# rf.net
KiCad netlist of a schematic drawn in Altium Designer
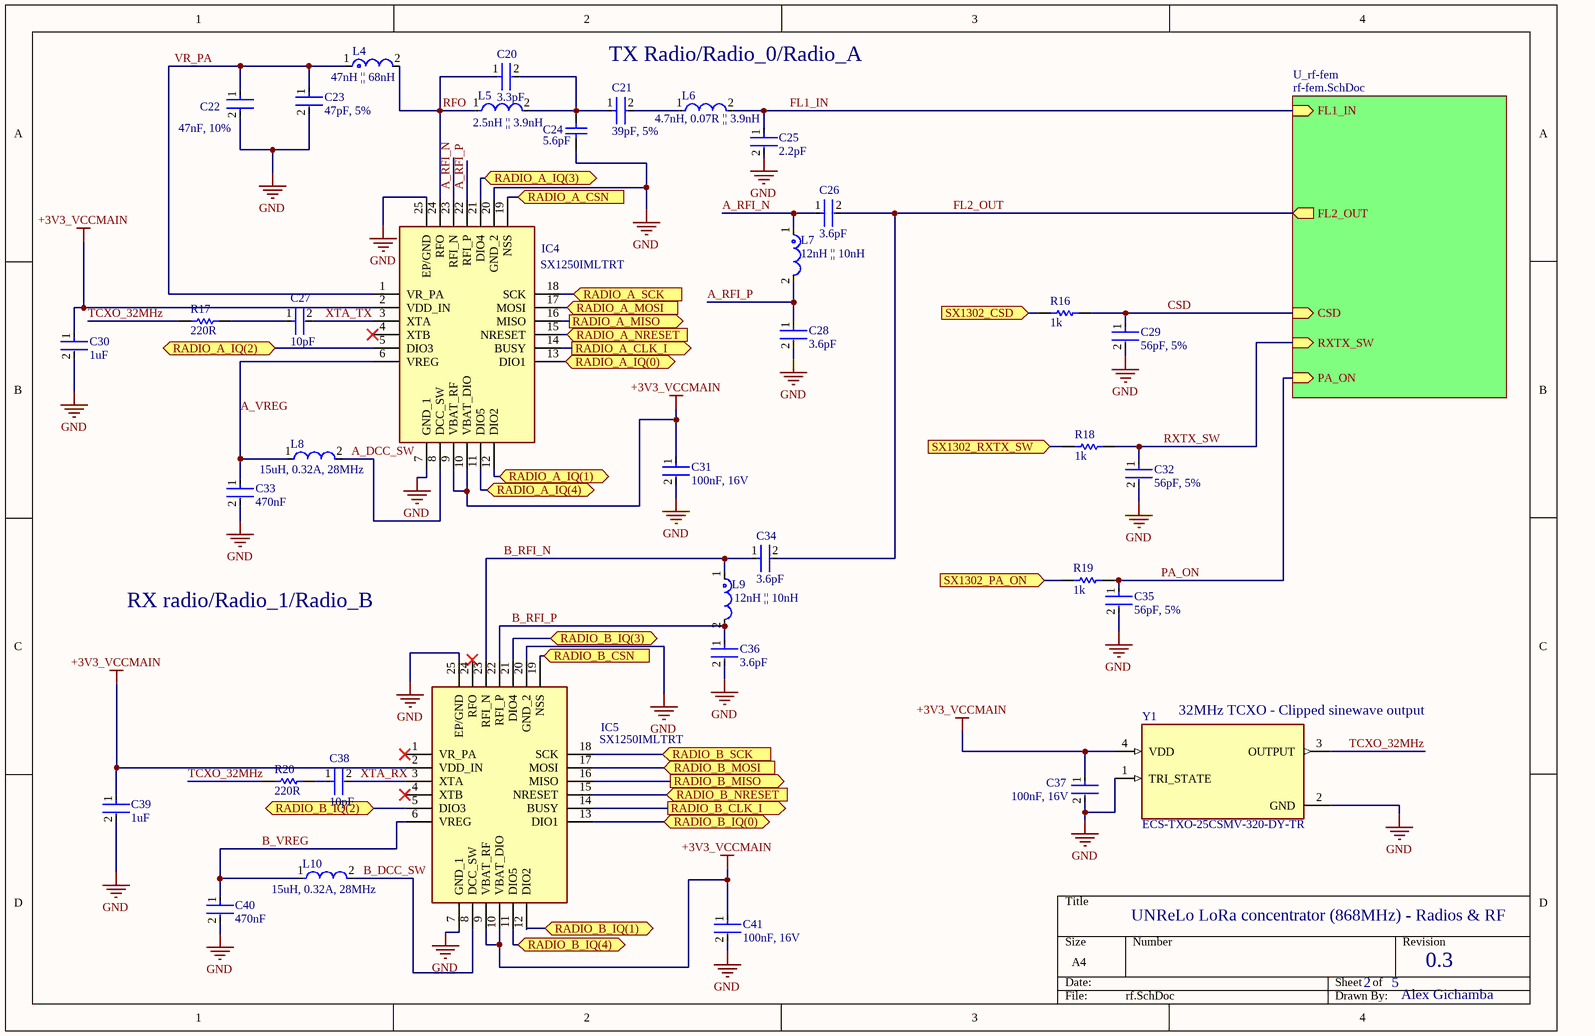
[diagram p0: rf.SchDoc]

(export (version "E")
  (design (tool "Eeschema 10.0.6"))
  (components
    (comp (ref "C20")
      (value "3.3pF")
      (footprint "FP-GQM187-0_15-MFG")
      (description "Ceramic Capacitor 3.3pF ±0.1pF 250VDC C0G 0603 Paper T/R")
      (libsource (lib "Altium Content Vault") (part "02cd4be3c70576c341d710602a673aa"))
    )
    (comp (ref "C21")
      (value "39pF, 5%")
      (footprint "FP-CL10-IPC_B")
      (description "Cap Ceramic 39pF 50V C0G ±5% Pad SMD 0603 +125°C T/R")
      (fields (field (name "TOLERANCE") "5%") (field (name "VOLTAGE") "50V"))
      (libsource (lib "Altium Content Vault") (part "b4654b650e69147ec39a6b967a45e02"))
    )
    (comp (ref "C22")
      (value "47nF, 10%")
      (footprint "FP-CL10-IPC_A")
      (description "Cap Ceramic 47nF 50V X7R ±10% Pad SMD 0603 +125°C T/R")
      (fields (field (name "TOLERANCE") "10%") (field (name "VOLTAGE") "50V"))
      (libsource (lib "Altium Content Vault") (part "b4654b650e69147ec39a6b967a45e02"))
    )
    (comp (ref "C23")
      (value "47pF, 5%")
      (footprint "FP-0603-L_1_6_0_15-W_0_81-MFG")
      (description "General Purpose Ceramic Capacitor, 0603, 47pF, 5%, NP0, 30ppm/°C, 50V")
      (fields (field (name "TOLERANCE") "5%") (field (name "VOLTAGE") "50V"))
      (libsource (lib "Altium Content Vault") (part "02cd4be3c70576c341d710602a673aa"))
    )
    (comp (ref "C24")
      (value "5.6pF")
      (footprint "CAPC1608X90X35ML10T15")
      (fields (field (name "MANUFACTURER") "Murata") (field (name "PART NUMBER") "GRM1885C1H5R6BA01D"))
      (libsource (lib "Altium Content Vault") (part "CAP"))
    )
    (comp (ref "C25")
      (value "2.2pF")
      (footprint "FP-CL764-IPC_C")
      (description "Cap Ceramic 2.2pF 50V C0G ±0.1pF SMD 0402 +125°C Paper T/R")
      (fields (field (name "VOLTAGE") "50V"))
      (libsource (lib "Altium Content Vault") (part "b4654b650e69147ec39a6b967a45e02"))
    )
    (comp (ref "C26")
      (value "3.6pF")
      (footprint "FP-GJM155-0_05-IPC_C")
      (description "Multi-Layer Ceramic Capacitor 3.6pF C0G  ±0.1pF 0402 Paper T/R")
      (libsource (lib "Altium Content Vault") (part "02cd4be3c70576c341d710602a673aa"))
    )
    (comp (ref "C27")
      (value "10pF")
      (footprint "FP-CL10-IPC_A")
      (description "Cap Ceramic 10pF 50V C0G ±5% Pad SMD 0603 +125°C T/R")
      (fields (field (name "VOLTAGE") "50V") (field (name "TOLERANCE") "5%"))
      (libsource (lib "Altium Content Vault") (part "b4654b650e69147ec39a6b967a45e02"))
    )
    (comp (ref "C28")
      (value "3.6pF")
      (footprint "FP-GJM155-0_05-IPC_C")
      (description "Multi-Layer Ceramic Capacitor 3.6pF C0G  ±0.1pF 0402 Paper T/R")
      (libsource (lib "Altium Content Vault") (part "02cd4be3c70576c341d710602a673aa"))
    )
    (comp (ref "C29")
      (value "56pF, 5%")
      (footprint "FP-GCM188-0_1-IPC_A")
      (description "Ceramic Capacitor for Automotive 56pF  ±5% 100VDC C0G 0603 Paper T/R")
      (fields (field (name "TOLERANCE") "5%"))
      (libsource (lib "Altium Content Vault") (part "02cd4be3c70576c341d710602a673aa"))
    )
    (comp (ref "C30")
      (value "1uF")
      (footprint "FP-CL21-IPC_A")
      (description "CL21 Series 0805 1uF 16V ±10% Tolerance X7R Multilayer Ceramic Chip Capacitor")
      (fields (field (name "TOLERANCE") "10%") (field (name "VOLTAGE") "16V"))
      (libsource (lib "Altium Content Vault") (part "b4654b650e69147ec39a6b967a45e02"))
    )
    (comp (ref "C31")
      (value "100nF, 16V")
      (footprint "FP-CC0603-DA-MFG")
      (description "CAP CER 0.1UF 50V X7R 0603")
      (fields (field (name "MANUFACTURER") "YAGEO") (field (name "VOLTAGE") "50 V"))
      (libsource (lib "Altium Content Vault") (part "11868f565c42a9108669ba33697ecf6"))
    )
    (comp (ref "C32")
      (value "56pF, 5%")
      (footprint "FP-GCM188-0_1-IPC_A")
      (description "Ceramic Capacitor for Automotive 56pF  ±5% 100VDC C0G 0603 Paper T/R")
      (fields (field (name "TOLERANCE") "5%"))
      (libsource (lib "Altium Content Vault") (part "02cd4be3c70576c341d710602a673aa"))
    )
    (comp (ref "C33")
      (value "470nF")
      (footprint "FP-0603-L_1_6_0_1-W_0_8_0-IPC_A")
      (description "None")
      (fields (field (name "TOLERANCE") "10%"))
      (libsource (lib "Altium Content Vault") (part "02cd4be3c70576c341d710602a673aa"))
    )
    (comp (ref "C34")
      (value "3.6pF")
      (footprint "FP-GJM155-0_05-IPC_C")
      (description "Multi-Layer Ceramic Capacitor 3.6pF C0G  ±0.1pF 0402 Paper T/R")
      (libsource (lib "Altium Content Vault") (part "02cd4be3c70576c341d710602a673aa"))
    )
    (comp (ref "C35")
      (value "56pF, 5%")
      (footprint "FP-GCM188-0_1-IPC_A")
      (description "Ceramic Capacitor for Automotive 56pF  ±5% 100VDC C0G 0603 Paper T/R")
      (fields (field (name "TOLERANCE") "5%"))
      (libsource (lib "Altium Content Vault") (part "02cd4be3c70576c341d710602a673aa"))
    )
    (comp (ref "C36")
      (value "3.6pF")
      (footprint "FP-GJM155-0_05-IPC_C")
      (description "Multi-Layer Ceramic Capacitor 3.6pF C0G  ±0.1pF 0402 Paper T/R")
      (libsource (lib "Altium Content Vault") (part "02cd4be3c70576c341d710602a673aa"))
    )
    (comp (ref "C37")
      (value "100nF, 16V")
      (footprint "FP-CC0603-DA-MFG")
      (description "CAP CER 0.1UF 50V X7R 0603")
      (fields (field (name "MANUFACTURER") "YAGEO") (field (name "VOLTAGE") "50 V"))
      (libsource (lib "Altium Content Vault") (part "11868f565c42a9108669ba33697ecf6"))
    )
    (comp (ref "C38")
      (value "10pF")
      (footprint "FP-CL10-IPC_A")
      (description "Cap Ceramic 10pF 50V C0G ±5% Pad SMD 0603 +125°C T/R")
      (fields (field (name "VOLTAGE") "50V") (field (name "TOLERANCE") "5%"))
      (libsource (lib "Altium Content Vault") (part "b4654b650e69147ec39a6b967a45e02"))
    )
    (comp (ref "C39")
      (value "1uF")
      (footprint "FP-CL21-IPC_A")
      (description "CL21 Series 0805 1uF 16V ±10% Tolerance X7R Multilayer Ceramic Chip Capacitor")
      (fields (field (name "TOLERANCE") "10%") (field (name "VOLTAGE") "16V"))
      (libsource (lib "Altium Content Vault") (part "b4654b650e69147ec39a6b967a45e02"))
    )
    (comp (ref "C40")
      (value "470nF")
      (footprint "FP-0603-L_1_6_0_1-W_0_8_0-IPC_A")
      (description "None")
      (fields (field (name "TOLERANCE") "10%"))
      (libsource (lib "Altium Content Vault") (part "02cd4be3c70576c341d710602a673aa"))
    )
    (comp (ref "C41")
      (value "100nF, 16V")
      (footprint "FP-CC0603-DA-MFG")
      (description "CAP CER 0.1UF 50V X7R 0603")
      (fields (field (name "MANUFACTURER") "YAGEO") (field (name "VOLTAGE") "50 V"))
      (libsource (lib "Altium Content Vault") (part "11868f565c42a9108669ba33697ecf6"))
    )
    (comp (ref "IC4")
      (value "SX1250IMLTRT")
      (footprint "QFN50P400X400X100-25N-D")
      (description "Integrated Circuit")
      (fields (field (name "MOUSER PART NUMBER") "947-SX1250IMLTRT"))
      (libsource (lib "SamacSys") (part "SX1250IMLTRT"))
    )
    (comp (ref "IC5")
      (value "SX1250IMLTRT")
      (footprint "QFN50P400X400X100-25N-D")
      (description "Integrated Circuit")
      (fields (field (name "MOUSER PART NUMBER") "947-SX1250IMLTRT"))
      (libsource (lib "SamacSys") (part "SX1250IMLTRT"))
    )
    (comp (ref "L4")
      (value "47nH Ζ 68nH")
      (footprint "FP-LQG18HH_00-MFG")
      (description "Multilayer type RF Inductor 68nH ±5% 0.8Ω 400mA 0603")
      (fields (field (name "TOLERANCE") "5%"))
      (libsource (lib "Altium Content Vault") (part "4cc4b267dca4c8e51f7102f422741d8"))
    )
    (comp (ref "L5")
      (value "2.5nH Ζ 3.9nH")
      (footprint "FP-LQW15AN_00-W0_6-0_1-MFG")
      (description "Wire Wound RF Inductor 4.7nH ±0.1nH 750mA 0.07Ω 0402 (1005)")
      (fields (field (name "TOLERANCE") "2%"))
      (libsource (lib "Altium Content Vault") (part "725321dda6339637d4d059423bc1c3c"))
    )
    (comp (ref "L6")
      (value "4.7nH, 0.07R Ζ 3.9nH")
      (footprint "FP-LQW15AN_00-W0_6-0_1-MFG")
      (description "Wire Wound RF Inductor 4.7nH ±0.1nH 750mA 0.07Ω 0402 (1005)")
      (fields (field (name "TOLERANCE") "2%"))
      (libsource (lib "Altium Content Vault") (part "725321dda6339637d4d059423bc1c3c"))
    )
    (comp (ref "L7")
      (value "12nH Ζ 10nH")
      (footprint "FP-LQG15HH_02-IPC_A")
      (description "Multilayer type RF Inductor 10nH ±5% 0.26Ω 500mA 0402")
      (fields (field (name "TOLERANCE") "5%"))
      (libsource (lib "Altium Content Vault") (part "4cc4b267dca4c8e51f7102f422741d8"))
    )
    (comp (ref "L8")
      (value "15uH, 0.32A, 28MHz")
      (footprint "FP-CB2012-MFG")
      (description "SMD Inductors 15uH ±10% 0.32A 1.69Ω 0805")
      (fields (field (name "TOLERANCE") "10%"))
      (libsource (lib "Altium Content Vault") (part "725321dda6339637d4d059423bc1c3c"))
    )
    (comp (ref "L9")
      (value "12nH Ζ 10nH")
      (footprint "FP-LQG15HH_02-IPC_A")
      (description "Multilayer type RF Inductor 10nH ±5% 0.26Ω 500mA 0402")
      (fields (field (name "TOLERANCE") "5%"))
      (libsource (lib "Altium Content Vault") (part "4cc4b267dca4c8e51f7102f422741d8"))
    )
    (comp (ref "L10")
      (value "15uH, 0.32A, 28MHz")
      (footprint "FP-CB2012-MFG")
      (description "SMD Inductors 15uH ±10% 0.32A 1.69Ω 0805")
      (fields (field (name "TOLERANCE") "10%"))
      (libsource (lib "Altium Content Vault") (part "725321dda6339637d4d059423bc1c3c"))
    )
    (comp (ref "R16")
      (value "1k")
      (footprint "RESC2013X70X40ML20T20")
      (description "Chip Resistor, 1 KOhm, +/- 1%, 0.125 W, -55 to 155 degC, 0805 (2012 Metric), RoHS, Tape and Reel")
      (fields (field (name "MANUFACTURER") "Panasonic"))
      (libsource (lib "Altium Content Vault") (part "RES-2"))
    )
    (comp (ref "R17")
      (value "220R")
      (footprint "RESC1608X55X30LL15T15")
      (description "Chip Resistor, 220 Ohm, +/- 1%, 0.1 W, -55 to 155 degC, 0603 (1608 Metric), RoHS, Tape and Reel")
      (fields (field (name "TOLERANCE") "1%"))
      (libsource (lib "Altium Content Vault") (part "RES-2"))
    )
    (comp (ref "R18")
      (value "1k")
      (footprint "RESC2013X70X40ML20T20")
      (description "Chip Resistor, 1 KOhm, +/- 1%, 0.125 W, -55 to 155 degC, 0805 (2012 Metric), RoHS, Tape and Reel")
      (fields (field (name "MANUFACTURER") "Panasonic"))
      (libsource (lib "Altium Content Vault") (part "RES-2"))
    )
    (comp (ref "R19")
      (value "1k")
      (footprint "RESC2013X70X40ML20T20")
      (description "Chip Resistor, 1 KOhm, +/- 1%, 0.125 W, -55 to 155 degC, 0805 (2012 Metric), RoHS, Tape and Reel")
      (fields (field (name "MANUFACTURER") "Panasonic"))
      (libsource (lib "Altium Content Vault") (part "RES-2"))
    )
    (comp (ref "R20")
      (value "220R")
      (footprint "RESC1608X55X30LL15T15")
      (description "Chip Resistor, 220 Ohm, +/- 1%, 0.1 W, -55 to 155 degC, 0603 (1608 Metric), RoHS, Tape and Reel")
      (fields (field (name "TOLERANCE") "1%"))
      (libsource (lib "Altium Content Vault") (part "RES-2"))
    )
    (comp (ref "Y1")
      (value "ECS-TXO-25CSMV-320-DY-TR")
      (footprint "OSC_ECS-TXO-25CSMV-320-DY-TR")
      (libsource (lib "ECS-TXO-25CSMV-320-DY-TR") (part "ECS-TXO-25CSMV-320-DY-TR"))
    )
  )
  (nets
    (net (code "1") (name "+3V3_VCCMAIN") (class "Default")
      (node (ref "C30") (pin "1") (pinfunction "1_1") (pintype "passive"))
      (node (ref "C31") (pin "1") (pinfunction "1_1") (pintype "passive"))
      (node (ref "C37") (pin "1") (pinfunction "1_1") (pintype "passive"))
      (node (ref "C39") (pin "1") (pinfunction "1_1") (pintype "passive"))
      (node (ref "C41") (pin "1") (pinfunction "1_1") (pintype "passive"))
      (node (ref "IC4") (pin "10") (pinfunction "VBAT_DIO_10") (pintype "passive"))
      (node (ref "IC4") (pin "2") (pinfunction "VDD_IN_2") (pintype "passive"))
      (node (ref "IC4") (pin "9") (pinfunction "VBAT_RF_9") (pintype "passive"))
      (node (ref "IC5") (pin "10") (pinfunction "VBAT_DIO_10") (pintype "passive"))
      (node (ref "IC5") (pin "2") (pinfunction "VDD_IN_2") (pintype "passive"))
      (node (ref "IC5") (pin "9") (pinfunction "VBAT_RF_9") (pintype "passive"))
      (node (ref "Y1") (pin "4") (pinfunction "VDD_4") (pintype "input"))
    )
    (net (code "2") (name "/A_DCC_SW") (class "Default")
      (node (ref "IC4") (pin "8") (pinfunction "DCC_SW_8") (pintype "passive"))
      (node (ref "L8") (pin "2") (pinfunction "2_2") (pintype "passive"))
    )
    (net (code "3") (name "/A_RFI_N") (class "Default")
      (node (ref "C26") (pin "1") (pinfunction "1_1") (pintype "passive"))
      (node (ref "IC4") (pin "23") (pinfunction "RFI_N_23") (pintype "passive"))
      (node (ref "L7") (pin "1") (pinfunction "1_1") (pintype "passive"))
    )
    (net (code "4") (name "/A_RFI_P") (class "Default")
      (node (ref "C28") (pin "1") (pinfunction "1_1") (pintype "passive"))
      (node (ref "IC4") (pin "22") (pinfunction "RFI_P_22") (pintype "passive"))
      (node (ref "L7") (pin "2") (pinfunction "2_2") (pintype "passive"))
    )
    (net (code "5") (name "/A_VREG") (class "Default")
      (node (ref "C33") (pin "1") (pinfunction "1_1") (pintype "passive"))
      (node (ref "IC4") (pin "6") (pinfunction "VREG_6") (pintype "passive"))
      (node (ref "L8") (pin "1") (pinfunction "1_1") (pintype "passive"))
    )
    (net (code "6") (name "/B_DCC_SW") (class "Default")
      (node (ref "IC5") (pin "8") (pinfunction "DCC_SW_8") (pintype "passive"))
      (node (ref "L10") (pin "2") (pinfunction "2_2") (pintype "passive"))
    )
    (net (code "7") (name "/B_RFI_N") (class "Default")
      (node (ref "C34") (pin "1") (pinfunction "1_1") (pintype "passive"))
      (node (ref "IC5") (pin "23") (pinfunction "RFI_N_23") (pintype "passive"))
      (node (ref "L9") (pin "1") (pinfunction "1_1") (pintype "passive"))
    )
    (net (code "8") (name "/B_RFI_P") (class "Default")
      (node (ref "C36") (pin "1") (pinfunction "1_1") (pintype "passive"))
      (node (ref "IC5") (pin "22") (pinfunction "RFI_P_22") (pintype "passive"))
      (node (ref "L9") (pin "2") (pinfunction "2_2") (pintype "passive"))
    )
    (net (code "9") (name "/B_VREG") (class "Default")
      (node (ref "C40") (pin "1") (pinfunction "1_1") (pintype "passive"))
      (node (ref "IC5") (pin "6") (pinfunction "VREG_6") (pintype "passive"))
      (node (ref "L10") (pin "1") (pinfunction "1_1") (pintype "passive"))
    )
    (net (code "10") (name "/CSD") (class "Default")
      (node (ref "C29") (pin "1") (pinfunction "1_1") (pintype "passive"))
      (node (ref "R16") (pin "2") (pinfunction "2_2") (pintype "passive"))
    )
    (net (code "11") (name "/FL1_IN") (class "Default")
      (node (ref "C25") (pin "1") (pinfunction "1_1") (pintype "passive"))
      (node (ref "L6") (pin "2") (pinfunction "2_2") (pintype "passive"))
    )
    (net (code "12") (name "/FL2_OUT") (class "Default")
      (node (ref "C26") (pin "2") (pinfunction "2_2") (pintype "passive"))
      (node (ref "C34") (pin "2") (pinfunction "2_2") (pintype "passive"))
    )
    (net (code "13") (name "/PA_ON") (class "Default")
      (node (ref "C35") (pin "1") (pinfunction "1_1") (pintype "passive"))
      (node (ref "R19") (pin "2") (pinfunction "2_2") (pintype "passive"))
    )
    (net (code "14") (name "/RADIO_A_CLK_I") (class "Default")
      (node (ref "IC4") (pin "14") (pinfunction "BUSY_14") (pintype "passive"))
    )
    (net (code "15") (name "/RADIO_A_CSN") (class "Default")
      (node (ref "IC4") (pin "19") (pinfunction "NSS_19") (pintype "passive"))
    )
    (net (code "16") (name "/RADIO_A_IQ(0)") (class "Default")
      (node (ref "IC4") (pin "13") (pinfunction "DIO1_13") (pintype "passive"))
    )
    (net (code "17") (name "/RADIO_A_IQ(1)") (class "Default")
      (node (ref "IC4") (pin "12") (pinfunction "DIO2_12") (pintype "passive"))
    )
    (net (code "18") (name "/RADIO_A_IQ(2)") (class "Default")
      (node (ref "IC4") (pin "5") (pinfunction "DIO3_5") (pintype "passive"))
    )
    (net (code "19") (name "/RADIO_A_IQ(3)") (class "Default")
      (node (ref "IC4") (pin "21") (pinfunction "DIO4_21") (pintype "passive"))
    )
    (net (code "20") (name "/RADIO_A_IQ(4)") (class "Default")
      (node (ref "IC4") (pin "11") (pinfunction "DIO5_11") (pintype "passive"))
    )
    (net (code "21") (name "/RADIO_A_MISO") (class "Default")
      (node (ref "IC4") (pin "16") (pinfunction "MISO_16") (pintype "passive"))
    )
    (net (code "22") (name "/RADIO_A_MOSI") (class "Default")
      (node (ref "IC4") (pin "17") (pinfunction "MOSI_17") (pintype "passive"))
    )
    (net (code "23") (name "/RADIO_A_NRESET") (class "Default")
      (node (ref "IC4") (pin "15") (pinfunction "NRESET_15") (pintype "passive"))
    )
    (net (code "24") (name "/RADIO_A_SCK") (class "Default")
      (node (ref "IC4") (pin "18") (pinfunction "SCK_18") (pintype "passive"))
    )
    (net (code "25") (name "/RADIO_B_CLK_I") (class "Default")
      (node (ref "IC5") (pin "14") (pinfunction "BUSY_14") (pintype "passive"))
    )
    (net (code "26") (name "/RADIO_B_CSN") (class "Default")
      (node (ref "IC5") (pin "19") (pinfunction "NSS_19") (pintype "passive"))
    )
    (net (code "27") (name "/RADIO_B_IQ(0)") (class "Default")
      (node (ref "IC5") (pin "13") (pinfunction "DIO1_13") (pintype "passive"))
    )
    (net (code "28") (name "/RADIO_B_IQ(1)") (class "Default")
      (node (ref "IC5") (pin "12") (pinfunction "DIO2_12") (pintype "passive"))
    )
    (net (code "29") (name "/RADIO_B_IQ(2)") (class "Default")
      (node (ref "IC5") (pin "5") (pinfunction "DIO3_5") (pintype "passive"))
    )
    (net (code "30") (name "/RADIO_B_IQ(3)") (class "Default")
      (node (ref "IC5") (pin "21") (pinfunction "DIO4_21") (pintype "passive"))
    )
    (net (code "31") (name "/RADIO_B_IQ(4)") (class "Default")
      (node (ref "IC5") (pin "11") (pinfunction "DIO5_11") (pintype "passive"))
    )
    (net (code "32") (name "/RADIO_B_MISO") (class "Default")
      (node (ref "IC5") (pin "16") (pinfunction "MISO_16") (pintype "passive"))
    )
    (net (code "33") (name "/RADIO_B_MOSI") (class "Default")
      (node (ref "IC5") (pin "17") (pinfunction "MOSI_17") (pintype "passive"))
    )
    (net (code "34") (name "/RADIO_B_NRESET") (class "Default")
      (node (ref "IC5") (pin "15") (pinfunction "NRESET_15") (pintype "passive"))
    )
    (net (code "35") (name "/RADIO_B_SCK") (class "Default")
      (node (ref "IC5") (pin "18") (pinfunction "SCK_18") (pintype "passive"))
    )
    (net (code "36") (name "/RFO") (class "Default")
      (node (ref "C20") (pin "1") (pinfunction "1_1") (pintype "passive"))
      (node (ref "IC4") (pin "24") (pinfunction "RFO_24") (pintype "passive"))
      (node (ref "L4") (pin "2") (pinfunction "2_2") (pintype "passive"))
      (node (ref "L5") (pin "1") (pinfunction "1_1") (pintype "passive"))
    )
    (net (code "37") (name "/RXTX_SW") (class "Default")
      (node (ref "C32") (pin "1") (pinfunction "1_1") (pintype "passive"))
      (node (ref "R18") (pin "2") (pinfunction "2_2") (pintype "passive"))
    )
    (net (code "38") (name "/SX1302_CSD") (class "Default")
      (node (ref "R16") (pin "1") (pinfunction "1_1") (pintype "passive"))
    )
    (net (code "39") (name "/SX1302_PA_ON") (class "Default")
      (node (ref "R19") (pin "1") (pinfunction "1_1") (pintype "passive"))
    )
    (net (code "40") (name "/SX1302_RXTX_SW") (class "Default")
      (node (ref "R18") (pin "1") (pinfunction "1_1") (pintype "passive"))
    )
    (net (code "41") (name "/TCXO_32MHz") (class "Default")
      (node (ref "R17") (pin "1") (pinfunction "1_1") (pintype "passive"))
      (node (ref "R20") (pin "1") (pinfunction "1_1") (pintype "passive"))
      (node (ref "Y1") (pin "3") (pinfunction "OUTPUT_3") (pintype "output"))
    )
    (net (code "42") (name "/VR_PA") (class "Default")
      (node (ref "C22") (pin "1") (pinfunction "1_1") (pintype "passive"))
      (node (ref "C23") (pin "1") (pinfunction "1_1") (pintype "passive"))
      (node (ref "IC4") (pin "1") (pinfunction "VR_PA_1") (pintype "passive"))
      (node (ref "L4") (pin "1") (pinfunction "1_1") (pintype "passive"))
    )
    (net (code "43") (name "/XTA_RX") (class "Default")
      (node (ref "C38") (pin "2") (pinfunction "2_2") (pintype "passive"))
      (node (ref "IC5") (pin "3") (pinfunction "XTA_3") (pintype "passive"))
    )
    (net (code "44") (name "/XTA_TX") (class "Default")
      (node (ref "C27") (pin "2") (pinfunction "2_2") (pintype "passive"))
      (node (ref "IC4") (pin "3") (pinfunction "XTA_3") (pintype "passive"))
    )
    (net (code "45") (name "GND") (class "Default")
      (node (ref "C22") (pin "2") (pinfunction "2_2") (pintype "passive"))
      (node (ref "C23") (pin "2") (pinfunction "2_2") (pintype "passive"))
      (node (ref "C24") (pin "1") (pinfunction "1_1") (pintype "passive"))
      (node (ref "C25") (pin "2") (pinfunction "2_2") (pintype "passive"))
      (node (ref "C28") (pin "2") (pinfunction "2_2") (pintype "passive"))
      (node (ref "C29") (pin "2") (pinfunction "2_2") (pintype "passive"))
      (node (ref "C30") (pin "2") (pinfunction "2_2") (pintype "passive"))
      (node (ref "C31") (pin "2") (pinfunction "2_2") (pintype "passive"))
      (node (ref "C32") (pin "2") (pinfunction "2_2") (pintype "passive"))
      (node (ref "C33") (pin "2") (pinfunction "2_2") (pintype "passive"))
      (node (ref "C35") (pin "2") (pinfunction "2_2") (pintype "passive"))
      (node (ref "C36") (pin "2") (pinfunction "2_2") (pintype "passive"))
      (node (ref "C37") (pin "2") (pinfunction "2_2") (pintype "passive"))
      (node (ref "C39") (pin "2") (pinfunction "2_2") (pintype "passive"))
      (node (ref "C40") (pin "2") (pinfunction "2_2") (pintype "passive"))
      (node (ref "C41") (pin "2") (pinfunction "2_2") (pintype "passive"))
      (node (ref "IC4") (pin "20") (pinfunction "GND_2_20") (pintype "passive"))
      (node (ref "IC4") (pin "25") (pinfunction "EP/GND_25") (pintype "passive"))
      (node (ref "IC4") (pin "7") (pinfunction "GND_1_7") (pintype "passive"))
      (node (ref "IC5") (pin "20") (pinfunction "GND_2_20") (pintype "passive"))
      (node (ref "IC5") (pin "25") (pinfunction "EP/GND_25") (pintype "passive"))
      (node (ref "IC5") (pin "7") (pinfunction "GND_1_7") (pintype "passive"))
      (node (ref "Y1") (pin "1") (pinfunction "TRI_STATE_1") (pintype "input"))
      (node (ref "Y1") (pin "2") (pinfunction "GND_2") (pintype "power_in"))
    )
    (net (code "46") (name "Net-(C20-Pad2)") (class "Default")
      (node (ref "C20") (pin "2") (pinfunction "2_2") (pintype "passive"))
      (node (ref "C21") (pin "1") (pinfunction "1_1") (pintype "passive"))
      (node (ref "C24") (pin "2") (pinfunction "2_2") (pintype "passive"))
      (node (ref "L5") (pin "2") (pinfunction "2_2") (pintype "passive"))
    )
    (net (code "47") (name "Net-(C21-Pad2)") (class "Default")
      (node (ref "C21") (pin "2") (pinfunction "2_2") (pintype "passive"))
      (node (ref "L6") (pin "1") (pinfunction "1_1") (pintype "passive"))
    )
    (net (code "48") (name "Net-(C27-Pad1)") (class "Default")
      (node (ref "C27") (pin "1") (pinfunction "1_1") (pintype "passive"))
      (node (ref "R17") (pin "2") (pinfunction "2_2") (pintype "passive"))
    )
    (net (code "49") (name "Net-(C38-Pad1)") (class "Default")
      (node (ref "C38") (pin "1") (pinfunction "1_1") (pintype "passive"))
      (node (ref "R20") (pin "2") (pinfunction "2_2") (pintype "passive"))
    )
    (net (code "50") (name "unconnected-(IC4-XTB-Pad4)") (class "Default")
      (node (ref "IC4") (pin "4") (pinfunction "XTB_4") (pintype "passive+no_connect"))
    )
    (net (code "51") (name "unconnected-(IC5-RFO-Pad24)") (class "Default")
      (node (ref "IC5") (pin "24") (pinfunction "RFO_24") (pintype "passive+no_connect"))
    )
    (net (code "52") (name "unconnected-(IC5-VR_PA-Pad1)") (class "Default")
      (node (ref "IC5") (pin "1") (pinfunction "VR_PA_1") (pintype "passive+no_connect"))
    )
    (net (code "53") (name "unconnected-(IC5-XTB-Pad4)") (class "Default")
      (node (ref "IC5") (pin "4") (pinfunction "XTB_4") (pintype "passive+no_connect"))
    )
  )
)
